# flossjtag.net
KiCad netlist of a schematic drawn in EAGLE
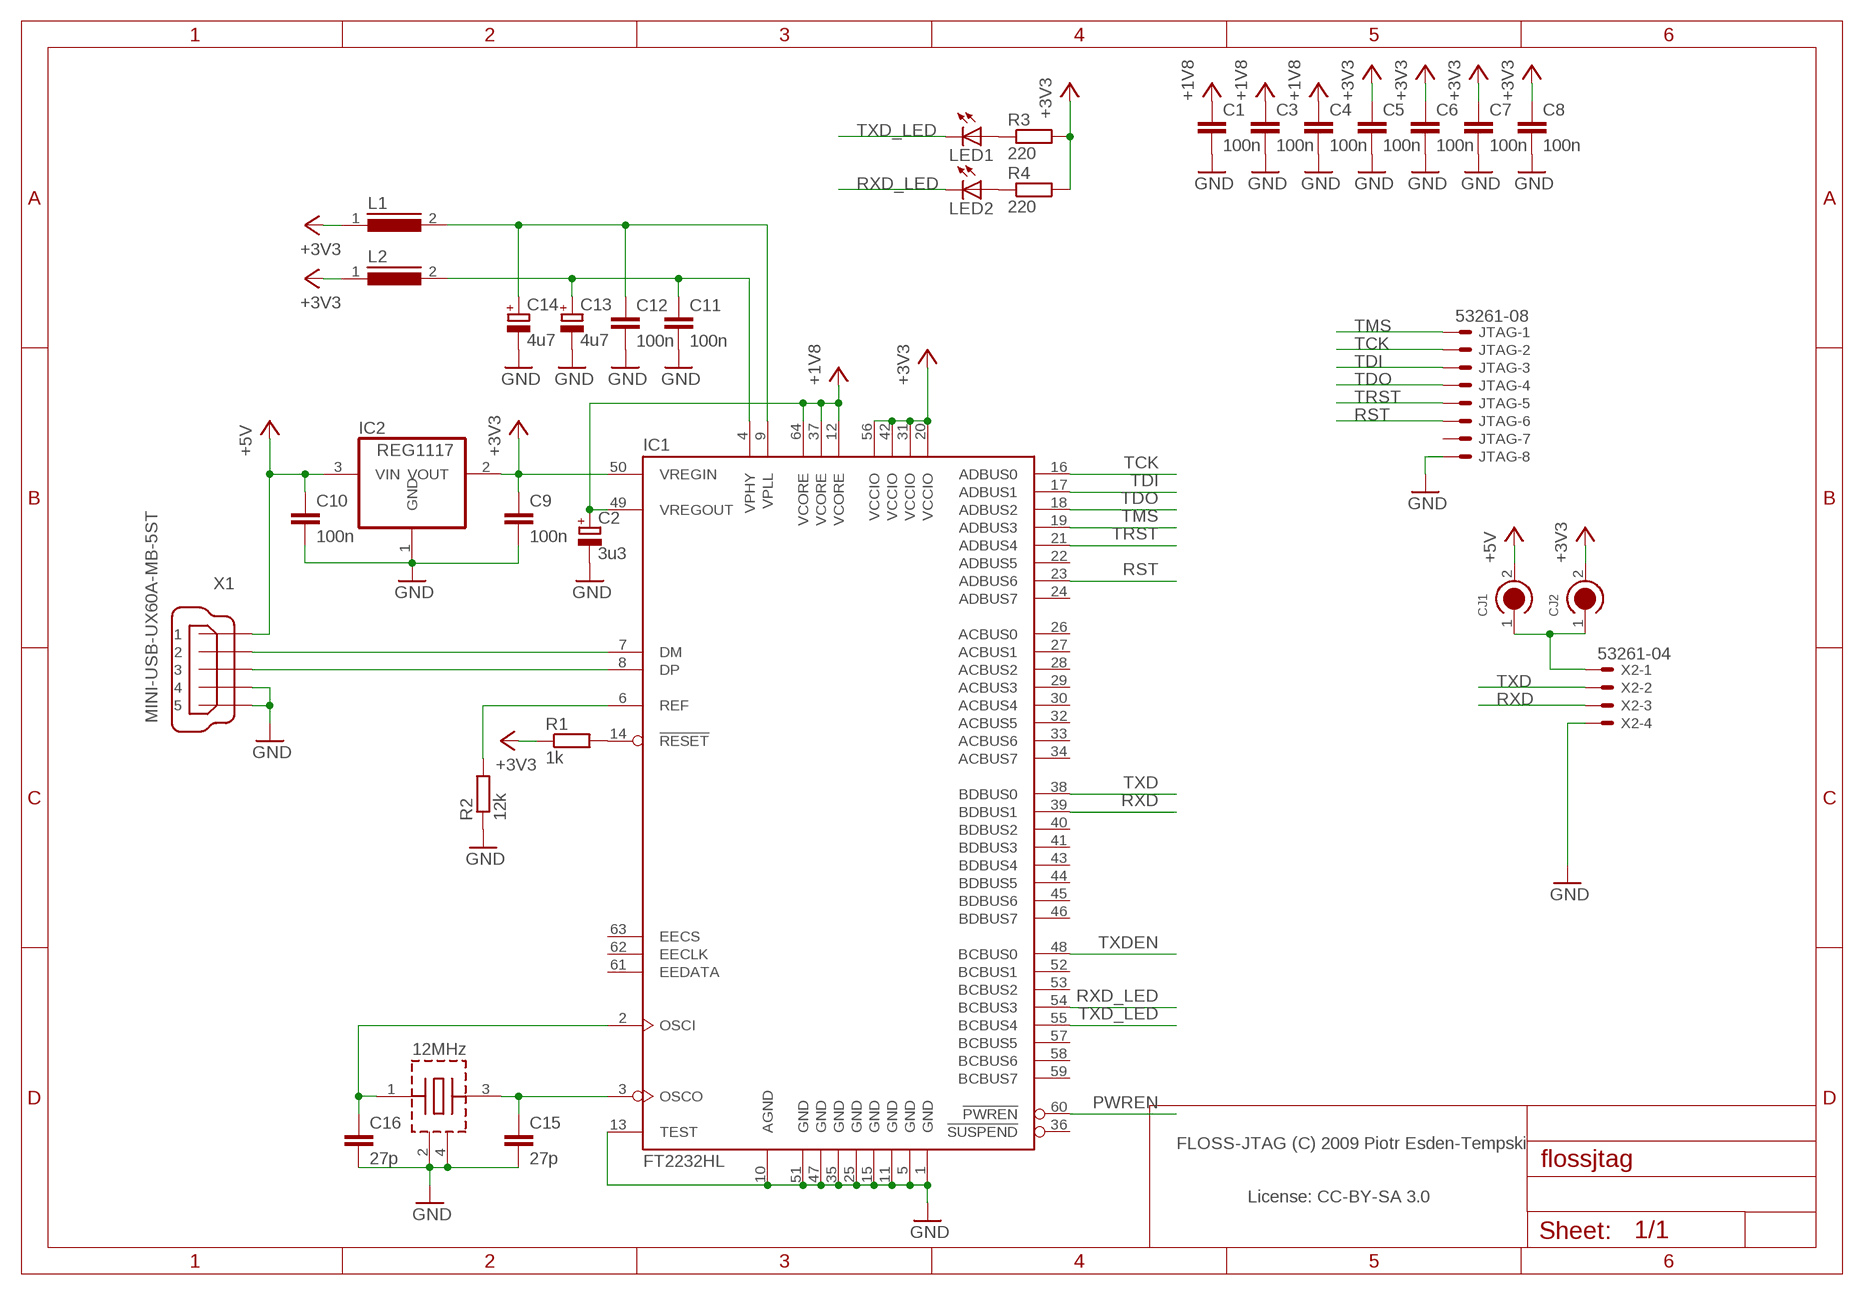
[diagram p0: schematic, sheet 1]

(export (version "E")
  (design (tool "Eeschema 10.0.6"))
  (components
    (comp (ref "C1")
      (value "100n")
      (footprint "eagle-import:C0603")
      (libsource (lib "eagle-import") (part "C-EUC0603"))
    )
    (comp (ref "C2")
      (value "3u3")
      (footprint "eagle-import:A_3216-18R")
      (libsource (lib "eagle-import") (part "CPOL-EUA/3216-18R"))
    )
    (comp (ref "C3")
      (value "100n")
      (footprint "eagle-import:C0603")
      (libsource (lib "eagle-import") (part "C-EUC0603"))
    )
    (comp (ref "C4")
      (value "100n")
      (footprint "eagle-import:C0603")
      (libsource (lib "eagle-import") (part "C-EUC0603"))
    )
    (comp (ref "C5")
      (value "100n")
      (footprint "eagle-import:C0603")
      (libsource (lib "eagle-import") (part "C-EUC0603"))
    )
    (comp (ref "C6")
      (value "100n")
      (footprint "eagle-import:C0603")
      (libsource (lib "eagle-import") (part "C-EUC0603"))
    )
    (comp (ref "C7")
      (value "100n")
      (footprint "eagle-import:C0603")
      (libsource (lib "eagle-import") (part "C-EUC0603"))
    )
    (comp (ref "C8")
      (value "100n")
      (footprint "eagle-import:C0603")
      (libsource (lib "eagle-import") (part "C-EUC0603"))
    )
    (comp (ref "C9")
      (value "100n")
      (footprint "eagle-import:C0603")
      (libsource (lib "eagle-import") (part "C-EUC0603"))
    )
    (comp (ref "C10")
      (value "100n")
      (footprint "eagle-import:C0603")
      (libsource (lib "eagle-import") (part "C-EUC0603"))
    )
    (comp (ref "C11")
      (value "100n")
      (footprint "eagle-import:C0603")
      (libsource (lib "eagle-import") (part "C-EUC0603"))
    )
    (comp (ref "C12")
      (value "100n")
      (footprint "eagle-import:C0603")
      (libsource (lib "eagle-import") (part "C-EUC0603"))
    )
    (comp (ref "C13")
      (value "4u7")
      (footprint "eagle-import:A_3216-18R")
      (libsource (lib "eagle-import") (part "CPOL-EUA/3216-18R"))
    )
    (comp (ref "C14")
      (value "4u7")
      (footprint "eagle-import:A_3216-18R")
      (libsource (lib "eagle-import") (part "CPOL-EUA/3216-18R"))
    )
    (comp (ref "C15")
      (value "27p")
      (footprint "eagle-import:C0603")
      (libsource (lib "eagle-import") (part "C-EUC0603"))
    )
    (comp (ref "C16")
      (value "27p")
      (footprint "eagle-import:C0603")
      (libsource (lib "eagle-import") (part "C-EUC0603"))
    )
    (comp (ref "CJ1")
      (value "CIRC_JMP")
      (footprint "eagle-import:CIRC_JMP")
      (libsource (lib "eagle-import") (part "CIRC_JMP"))
    )
    (comp (ref "CJ2")
      (value "CIRC_JMP")
      (footprint "eagle-import:CIRC_JMP")
      (libsource (lib "eagle-import") (part "CIRC_JMP"))
    )
    (comp (ref "IC1")
      (value "FT2232HL")
      (footprint "eagle-import:LQFP64")
      (libsource (lib "eagle-import") (part "FT2232HL"))
    )
    (comp (ref "IC2")
      (value "REG1117")
      (footprint "eagle-import:SOT223")
      (libsource (lib "eagle-import") (part "REG1117"))
    )
    (comp (ref "JTAG")
      (value "53261-08")
      (footprint "eagle-import:53261-08")
      (libsource (lib "eagle-import") (part "53?-08261"))
    )
    (comp (ref "L1")
      (value "I0603")
      (footprint "eagle-import:R0603")
      (libsource (lib "eagle-import") (part "I0603"))
    )
    (comp (ref "L2")
      (value "I0603")
      (footprint "eagle-import:R0603")
      (libsource (lib "eagle-import") (part "I0603"))
    )
    (comp (ref "LED1")
      (value "LEDCHIP-LED0603")
      (footprint "eagle-import:CHIP-LED0603")
      (libsource (lib "eagle-import") (part "LEDCHIP-LED0603"))
    )
    (comp (ref "LED2")
      (value "LEDCHIP-LED0603")
      (footprint "eagle-import:CHIP-LED0603")
      (libsource (lib "eagle-import") (part "LEDCHIP-LED0603"))
    )
    (comp (ref "R1")
      (value "1k")
      (footprint "eagle-import:R0603")
      (libsource (lib "eagle-import") (part "R-EU_R0603"))
    )
    (comp (ref "R2")
      (value "12k")
      (footprint "eagle-import:R0603")
      (libsource (lib "eagle-import") (part "R-EU_R0603"))
    )
    (comp (ref "R3")
      (value "220")
      (footprint "eagle-import:R0603")
      (libsource (lib "eagle-import") (part "R-EU_R0603"))
    )
    (comp (ref "R4")
      (value "220")
      (footprint "eagle-import:R0603")
      (libsource (lib "eagle-import") (part "R-EU_R0603"))
    )
    (comp (ref "X1")
      (value "MINI-USB-UX60A-MB-5ST")
      (footprint "eagle-import:UX60A-MB-5ST")
      (libsource (lib "eagle-import") (part "MINI-USB-UX60A-MB-5ST"))
    )
    (comp (ref "X2")
      (value "53261-04")
      (footprint "eagle-import:53261-04")
      (libsource (lib "eagle-import") (part "53?-04261"))
    )
    (comp (ref "X3")
      (value "12MHz")
      (footprint "eagle-import:NX3225SA")
      (libsource (lib "eagle-import") (part "NX3225SA"))
    )
  )
  (nets
    (net (code "1") (name "+1V8") (class "Default")
      (node (ref "C1") (pin "1") (pinfunction "1_1") (pintype "passive"))
      (node (ref "C2") (pin "+") (pinfunction "+_+") (pintype "passive"))
      (node (ref "C3") (pin "1") (pinfunction "1_1") (pintype "passive"))
      (node (ref "C4") (pin "1") (pinfunction "1_1") (pintype "passive"))
      (node (ref "IC1") (pin "12") (pinfunction "VCORE_12") (pintype "bidirectional"))
      (node (ref "IC1") (pin "37") (pinfunction "VCORE_37") (pintype "bidirectional"))
      (node (ref "IC1") (pin "49") (pinfunction "VREGOUT_49") (pintype "bidirectional"))
      (node (ref "IC1") (pin "64") (pinfunction "VCORE_64") (pintype "bidirectional"))
    )
    (net (code "2") (name "+3V3") (class "Default")
      (node (ref "C5") (pin "1") (pinfunction "1_1") (pintype "passive"))
      (node (ref "C6") (pin "1") (pinfunction "1_1") (pintype "passive"))
      (node (ref "C7") (pin "1") (pinfunction "1_1") (pintype "passive"))
      (node (ref "C8") (pin "1") (pinfunction "1_1") (pintype "passive"))
      (node (ref "C9") (pin "1") (pinfunction "1_1") (pintype "passive"))
      (node (ref "CJ2") (pin "2") (pinfunction "P$2_2") (pintype "bidirectional"))
      (node (ref "IC1") (pin "20") (pinfunction "VCCIO_20") (pintype "bidirectional"))
      (node (ref "IC1") (pin "31") (pinfunction "VCCIO_31") (pintype "bidirectional"))
      (node (ref "IC1") (pin "42") (pinfunction "VCCIO_42") (pintype "bidirectional"))
      (node (ref "IC1") (pin "50") (pinfunction "VREGIN_50") (pintype "bidirectional"))
      (node (ref "IC1") (pin "56") (pinfunction "VCCIO_56") (pintype "bidirectional"))
      (node (ref "IC2") (pin "2") (pinfunction "VOUT_2") (pintype "output"))
      (node (ref "L1") (pin "1") (pinfunction "1_1") (pintype "passive"))
      (node (ref "L2") (pin "1") (pinfunction "1_1") (pintype "passive"))
      (node (ref "R1") (pin "1") (pinfunction "1_1") (pintype "passive"))
      (node (ref "R3") (pin "2") (pinfunction "2_2") (pintype "passive"))
      (node (ref "R4") (pin "2") (pinfunction "2_2") (pintype "passive"))
    )
    (net (code "3") (name "+5V") (class "Default")
      (node (ref "C10") (pin "1") (pinfunction "1_1") (pintype "passive"))
      (node (ref "CJ1") (pin "2") (pinfunction "P$2_2") (pintype "bidirectional"))
      (node (ref "IC2") (pin "3") (pinfunction "VIN_3") (pintype "input"))
      (node (ref "X1") (pin "1") (pinfunction "1_1") (pintype "input"))
    )
    (net (code "4") (name "/PWREN") (class "Default")
      (node (ref "IC1") (pin "60") (pinfunction "~{PWREN}_60") (pintype "bidirectional"))
    )
    (net (code "5") (name "/RST") (class "Default")
      (node (ref "IC1") (pin "23") (pinfunction "ADBUS6_23") (pintype "bidirectional"))
      (node (ref "JTAG") (pin "6") (pinfunction "S_6") (pintype "passive"))
    )
    (net (code "6") (name "/RXD") (class "Default")
      (node (ref "IC1") (pin "39") (pinfunction "BDBUS1_39") (pintype "bidirectional"))
      (node (ref "X2") (pin "3") (pinfunction "S_3") (pintype "passive"))
    )
    (net (code "7") (name "/RXD_LED") (class "Default")
      (node (ref "IC1") (pin "54") (pinfunction "BCBUS3_54") (pintype "bidirectional"))
      (node (ref "LED2") (pin "C") (pinfunction "C_C") (pintype "passive"))
    )
    (net (code "8") (name "/TCK") (class "Default")
      (node (ref "IC1") (pin "16") (pinfunction "ADBUS0_16") (pintype "bidirectional"))
      (node (ref "JTAG") (pin "2") (pinfunction "S_2") (pintype "passive"))
    )
    (net (code "9") (name "/TDI") (class "Default")
      (node (ref "IC1") (pin "17") (pinfunction "ADBUS1_17") (pintype "bidirectional"))
      (node (ref "JTAG") (pin "3") (pinfunction "S_3") (pintype "passive"))
    )
    (net (code "10") (name "/TDO") (class "Default")
      (node (ref "IC1") (pin "18") (pinfunction "ADBUS2_18") (pintype "bidirectional"))
      (node (ref "JTAG") (pin "4") (pinfunction "S_4") (pintype "passive"))
    )
    (net (code "11") (name "/TMS") (class "Default")
      (node (ref "IC1") (pin "19") (pinfunction "ADBUS3_19") (pintype "bidirectional"))
      (node (ref "JTAG") (pin "1") (pinfunction "S_1") (pintype "passive"))
    )
    (net (code "12") (name "/TRST") (class "Default")
      (node (ref "IC1") (pin "21") (pinfunction "ADBUS4_21") (pintype "bidirectional"))
      (node (ref "JTAG") (pin "5") (pinfunction "S_5") (pintype "passive"))
    )
    (net (code "13") (name "/TXD") (class "Default")
      (node (ref "IC1") (pin "38") (pinfunction "BDBUS0_38") (pintype "bidirectional"))
      (node (ref "X2") (pin "2") (pinfunction "S_2") (pintype "passive"))
    )
    (net (code "14") (name "/TXDEN") (class "Default")
      (node (ref "IC1") (pin "48") (pinfunction "BCBUS0_48") (pintype "bidirectional"))
    )
    (net (code "15") (name "/TXD_LED") (class "Default")
      (node (ref "IC1") (pin "55") (pinfunction "BCBUS4_55") (pintype "bidirectional"))
      (node (ref "LED1") (pin "C") (pinfunction "C_C") (pintype "passive"))
    )
    (net (code "16") (name "GND") (class "Default")
      (node (ref "C1") (pin "2") (pinfunction "2_2") (pintype "passive"))
      (node (ref "C10") (pin "2") (pinfunction "2_2") (pintype "passive"))
      (node (ref "C11") (pin "2") (pinfunction "2_2") (pintype "passive"))
      (node (ref "C12") (pin "2") (pinfunction "2_2") (pintype "passive"))
      (node (ref "C13") (pin "-") (pinfunction "-_-") (pintype "passive"))
      (node (ref "C14") (pin "-") (pinfunction "-_-") (pintype "passive"))
      (node (ref "C15") (pin "2") (pinfunction "2_2") (pintype "passive"))
      (node (ref "C16") (pin "2") (pinfunction "2_2") (pintype "passive"))
      (node (ref "C2") (pin "-") (pinfunction "-_-") (pintype "passive"))
      (node (ref "C3") (pin "2") (pinfunction "2_2") (pintype "passive"))
      (node (ref "C4") (pin "2") (pinfunction "2_2") (pintype "passive"))
      (node (ref "C5") (pin "2") (pinfunction "2_2") (pintype "passive"))
      (node (ref "C6") (pin "2") (pinfunction "2_2") (pintype "passive"))
      (node (ref "C7") (pin "2") (pinfunction "2_2") (pintype "passive"))
      (node (ref "C8") (pin "2") (pinfunction "2_2") (pintype "passive"))
      (node (ref "C9") (pin "2") (pinfunction "2_2") (pintype "passive"))
      (node (ref "IC1") (pin "1") (pinfunction "GND_1") (pintype "bidirectional"))
      (node (ref "IC1") (pin "10") (pinfunction "AGND_10") (pintype "bidirectional"))
      (node (ref "IC1") (pin "11") (pinfunction "GND_11") (pintype "bidirectional"))
      (node (ref "IC1") (pin "13") (pinfunction "TEST_13") (pintype "bidirectional"))
      (node (ref "IC1") (pin "15") (pinfunction "GND_15") (pintype "bidirectional"))
      (node (ref "IC1") (pin "25") (pinfunction "GND_25") (pintype "bidirectional"))
      (node (ref "IC1") (pin "35") (pinfunction "GND_35") (pintype "bidirectional"))
      (node (ref "IC1") (pin "47") (pinfunction "GND_47") (pintype "bidirectional"))
      (node (ref "IC1") (pin "5") (pinfunction "GND_5") (pintype "bidirectional"))
      (node (ref "IC1") (pin "51") (pinfunction "GND_51") (pintype "bidirectional"))
      (node (ref "IC2") (pin "1") (pinfunction "GND_1") (pintype "power_in"))
      (node (ref "JTAG") (pin "8") (pinfunction "S_8") (pintype "passive"))
      (node (ref "R2") (pin "1") (pinfunction "1_1") (pintype "passive"))
      (node (ref "X1") (pin "4") (pinfunction "4_4") (pintype "input"))
      (node (ref "X1") (pin "5") (pinfunction "5_5") (pintype "input"))
      (node (ref "X2") (pin "4") (pinfunction "S_4") (pintype "passive"))
      (node (ref "X3") (pin "2") (pinfunction "GND_2") (pintype "bidirectional"))
      (node (ref "X3") (pin "4") (pinfunction "GND_4") (pintype "bidirectional"))
    )
    (net (code "17") (name "Net-(CJ1-P$1)") (class "Default")
      (node (ref "CJ1") (pin "1") (pinfunction "P$1_1") (pintype "bidirectional"))
      (node (ref "CJ2") (pin "1") (pinfunction "P$1_1") (pintype "bidirectional"))
      (node (ref "X2") (pin "1") (pinfunction "S_1") (pintype "passive"))
    )
    (net (code "18") (name "Net-(IC1-DM)") (class "Default")
      (node (ref "IC1") (pin "7") (pinfunction "DM_7") (pintype "bidirectional"))
      (node (ref "X1") (pin "2") (pinfunction "2_2") (pintype "input"))
    )
    (net (code "19") (name "Net-(IC1-DP)") (class "Default")
      (node (ref "IC1") (pin "8") (pinfunction "DP_8") (pintype "bidirectional"))
      (node (ref "X1") (pin "3") (pinfunction "3_3") (pintype "input"))
    )
    (net (code "20") (name "Net-(IC1-OSCI)") (class "Default")
      (node (ref "C16") (pin "1") (pinfunction "1_1") (pintype "passive"))
      (node (ref "IC1") (pin "2") (pinfunction "OSCI_2") (pintype "bidirectional"))
      (node (ref "X3") (pin "1") (pinfunction "XTAL_1") (pintype "bidirectional"))
    )
    (net (code "21") (name "Net-(IC1-OSCO)") (class "Default")
      (node (ref "C15") (pin "1") (pinfunction "1_1") (pintype "passive"))
      (node (ref "IC1") (pin "3") (pinfunction "OSCO_3") (pintype "bidirectional"))
      (node (ref "X3") (pin "3") (pinfunction "XTAL_3") (pintype "bidirectional"))
    )
    (net (code "22") (name "Net-(IC1-REF)") (class "Default")
      (node (ref "IC1") (pin "6") (pinfunction "REF_6") (pintype "bidirectional"))
      (node (ref "R2") (pin "2") (pinfunction "2_2") (pintype "passive"))
    )
    (net (code "23") (name "Net-(IC1-VPHY)") (class "Default")
      (node (ref "C11") (pin "1") (pinfunction "1_1") (pintype "passive"))
      (node (ref "C13") (pin "+") (pinfunction "+_+") (pintype "passive"))
      (node (ref "IC1") (pin "4") (pinfunction "VPHY_4") (pintype "bidirectional"))
      (node (ref "L2") (pin "2") (pinfunction "2_2") (pintype "passive"))
    )
    (net (code "24") (name "Net-(IC1-VPLL)") (class "Default")
      (node (ref "C12") (pin "1") (pinfunction "1_1") (pintype "passive"))
      (node (ref "C14") (pin "+") (pinfunction "+_+") (pintype "passive"))
      (node (ref "IC1") (pin "9") (pinfunction "VPLL_9") (pintype "bidirectional"))
      (node (ref "L1") (pin "2") (pinfunction "2_2") (pintype "passive"))
    )
    (net (code "25") (name "Net-(IC1-~{RESET})") (class "Default")
      (node (ref "IC1") (pin "14") (pinfunction "~{RESET}_14") (pintype "bidirectional"))
      (node (ref "R1") (pin "2") (pinfunction "2_2") (pintype "passive"))
    )
    (net (code "26") (name "Net-(LED1-PadA)") (class "Default")
      (node (ref "LED1") (pin "A") (pinfunction "A_A") (pintype "passive"))
      (node (ref "R3") (pin "1") (pinfunction "1_1") (pintype "passive"))
    )
    (net (code "27") (name "Net-(LED2-PadA)") (class "Default")
      (node (ref "LED2") (pin "A") (pinfunction "A_A") (pintype "passive"))
      (node (ref "R4") (pin "1") (pinfunction "1_1") (pintype "passive"))
    )
    (net (code "28") (name "unconnected-(IC1-ACBUS0-Pad26)") (class "Default")
      (node (ref "IC1") (pin "26") (pinfunction "ACBUS0_26") (pintype "bidirectional"))
    )
    (net (code "29") (name "unconnected-(IC1-ACBUS1-Pad27)") (class "Default")
      (node (ref "IC1") (pin "27") (pinfunction "ACBUS1_27") (pintype "bidirectional"))
    )
    (net (code "30") (name "unconnected-(IC1-ACBUS2-Pad28)") (class "Default")
      (node (ref "IC1") (pin "28") (pinfunction "ACBUS2_28") (pintype "bidirectional"))
    )
    (net (code "31") (name "unconnected-(IC1-ACBUS3-Pad29)") (class "Default")
      (node (ref "IC1") (pin "29") (pinfunction "ACBUS3_29") (pintype "bidirectional"))
    )
    (net (code "32") (name "unconnected-(IC1-ACBUS4-Pad30)") (class "Default")
      (node (ref "IC1") (pin "30") (pinfunction "ACBUS4_30") (pintype "bidirectional"))
    )
    (net (code "33") (name "unconnected-(IC1-ACBUS5-Pad32)") (class "Default")
      (node (ref "IC1") (pin "32") (pinfunction "ACBUS5_32") (pintype "bidirectional"))
    )
    (net (code "34") (name "unconnected-(IC1-ACBUS6-Pad33)") (class "Default")
      (node (ref "IC1") (pin "33") (pinfunction "ACBUS6_33") (pintype "bidirectional"))
    )
    (net (code "35") (name "unconnected-(IC1-ACBUS7-Pad34)") (class "Default")
      (node (ref "IC1") (pin "34") (pinfunction "ACBUS7_34") (pintype "bidirectional"))
    )
    (net (code "36") (name "unconnected-(IC1-ADBUS5-Pad22)") (class "Default")
      (node (ref "IC1") (pin "22") (pinfunction "ADBUS5_22") (pintype "bidirectional"))
    )
    (net (code "37") (name "unconnected-(IC1-ADBUS7-Pad24)") (class "Default")
      (node (ref "IC1") (pin "24") (pinfunction "ADBUS7_24") (pintype "bidirectional"))
    )
    (net (code "38") (name "unconnected-(IC1-BCBUS1-Pad52)") (class "Default")
      (node (ref "IC1") (pin "52") (pinfunction "BCBUS1_52") (pintype "bidirectional"))
    )
    (net (code "39") (name "unconnected-(IC1-BCBUS2-Pad53)") (class "Default")
      (node (ref "IC1") (pin "53") (pinfunction "BCBUS2_53") (pintype "bidirectional"))
    )
    (net (code "40") (name "unconnected-(IC1-BCBUS5-Pad57)") (class "Default")
      (node (ref "IC1") (pin "57") (pinfunction "BCBUS5_57") (pintype "bidirectional"))
    )
    (net (code "41") (name "unconnected-(IC1-BCBUS6-Pad58)") (class "Default")
      (node (ref "IC1") (pin "58") (pinfunction "BCBUS6_58") (pintype "bidirectional"))
    )
    (net (code "42") (name "unconnected-(IC1-BCBUS7-Pad59)") (class "Default")
      (node (ref "IC1") (pin "59") (pinfunction "BCBUS7_59") (pintype "bidirectional"))
    )
    (net (code "43") (name "unconnected-(IC1-BDBUS2-Pad40)") (class "Default")
      (node (ref "IC1") (pin "40") (pinfunction "BDBUS2_40") (pintype "bidirectional"))
    )
    (net (code "44") (name "unconnected-(IC1-BDBUS3-Pad41)") (class "Default")
      (node (ref "IC1") (pin "41") (pinfunction "BDBUS3_41") (pintype "bidirectional"))
    )
    (net (code "45") (name "unconnected-(IC1-BDBUS4-Pad43)") (class "Default")
      (node (ref "IC1") (pin "43") (pinfunction "BDBUS4_43") (pintype "bidirectional"))
    )
    (net (code "46") (name "unconnected-(IC1-BDBUS5-Pad44)") (class "Default")
      (node (ref "IC1") (pin "44") (pinfunction "BDBUS5_44") (pintype "bidirectional"))
    )
    (net (code "47") (name "unconnected-(IC1-BDBUS6-Pad45)") (class "Default")
      (node (ref "IC1") (pin "45") (pinfunction "BDBUS6_45") (pintype "bidirectional"))
    )
    (net (code "48") (name "unconnected-(IC1-BDBUS7-Pad46)") (class "Default")
      (node (ref "IC1") (pin "46") (pinfunction "BDBUS7_46") (pintype "bidirectional"))
    )
    (net (code "49") (name "unconnected-(IC1-EECLK-Pad62)") (class "Default")
      (node (ref "IC1") (pin "62") (pinfunction "EECLK_62") (pintype "bidirectional"))
    )
    (net (code "50") (name "unconnected-(IC1-EECS-Pad63)") (class "Default")
      (node (ref "IC1") (pin "63") (pinfunction "EECS_63") (pintype "bidirectional"))
    )
    (net (code "51") (name "unconnected-(IC1-EEDATA-Pad61)") (class "Default")
      (node (ref "IC1") (pin "61") (pinfunction "EEDATA_61") (pintype "bidirectional"))
    )
    (net (code "52") (name "unconnected-(IC1-~{SUSPEND}-Pad36)") (class "Default")
      (node (ref "IC1") (pin "36") (pinfunction "~{SUSPEND}_36") (pintype "bidirectional"))
    )
    (net (code "53") (name "unconnected-(JTAGG-S-Pad7)") (class "Default")
      (node (ref "JTAG") (pin "7") (pinfunction "S_7") (pintype "passive"))
    )
  )
)
